# 1_SheetMain.net
KiCad netlist of a schematic drawn in Altium Designer
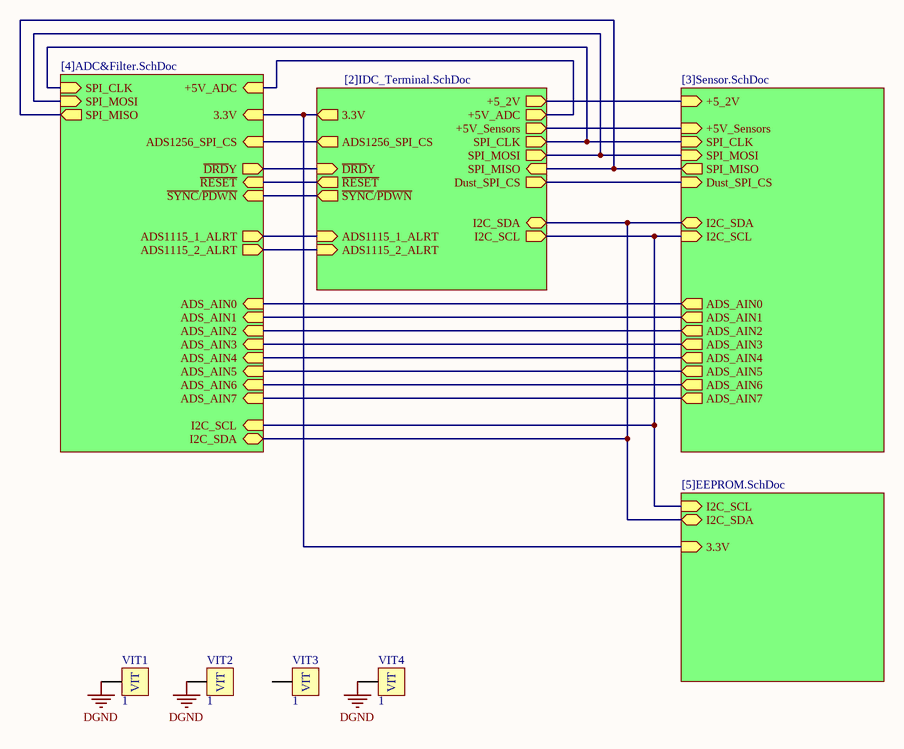
[diagram p0: [1]SheetMain.SchDoc]

(export (version "E")
  (design (tool "Eeschema 10.0.6"))
  (components
    (comp (ref "VIT1")
      (value "1")
      (footprint "Connector:Screw Hole 4mm")
      (description "Vit xuyen lo")
      (libsource (lib "Connector") (part "VIT"))
    )
    (comp (ref "VIT2")
      (value "1")
      (footprint "Connector:Screw Hole 4mm")
      (description "Vit xuyen lo")
      (libsource (lib "Connector") (part "VIT"))
    )
    (comp (ref "VIT3")
      (value "1")
      (footprint "Connector:Screw Hole 4mm")
      (description "Vit xuyen lo")
      (libsource (lib "Connector") (part "VIT"))
    )
    (comp (ref "VIT4")
      (value "1")
      (footprint "Connector:Screw Hole 4mm")
      (description "Vit xuyen lo")
      (libsource (lib "Connector") (part "VIT"))
    )
  )
  (nets
    (net (code "25") (name "DGND") (class "Default")
      (node (ref "VIT1") (pin "1") (pinfunction "1_1") (pintype "passive"))
      (node (ref "VIT2") (pin "1") (pinfunction "1_1") (pintype "passive"))
      (node (ref "VIT4") (pin "1") (pinfunction "1_1") (pintype "passive"))
    )
    (net (code "26") (name "unconnected-(VIT3-Pad1)") (class "Default")
      (node (ref "VIT3") (pin "1") (pinfunction "1_1") (pintype "passive"))
    )
  )
)
